# ardugilla-ver8.net
KiCad netlist of a schematic drawn in EAGLE
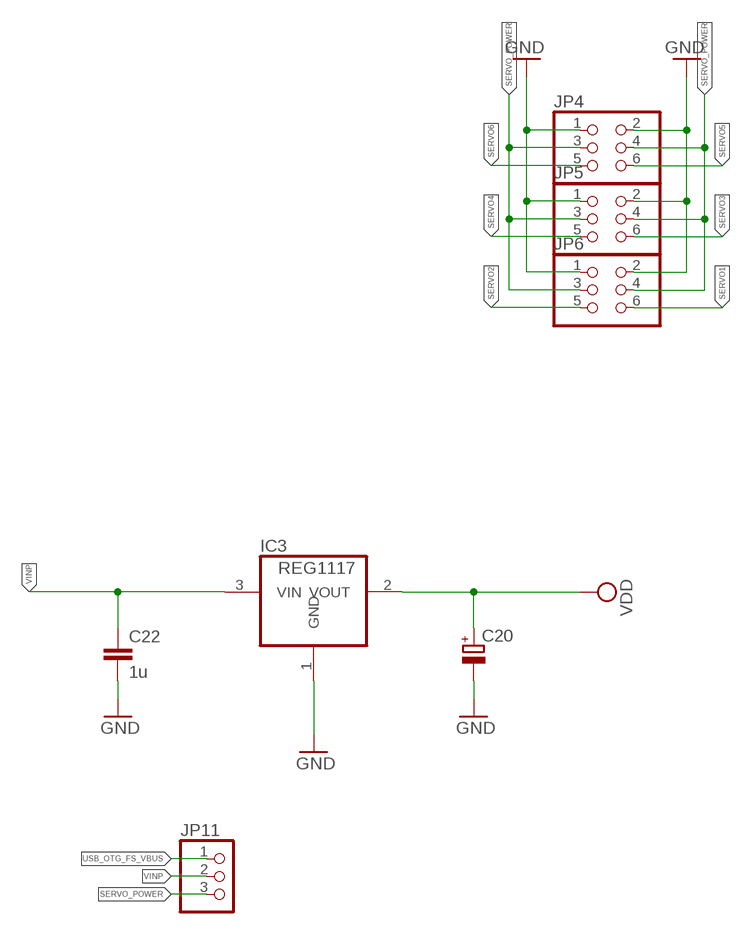
[diagram p0: schematic, sheet 1, part 1 of 2]
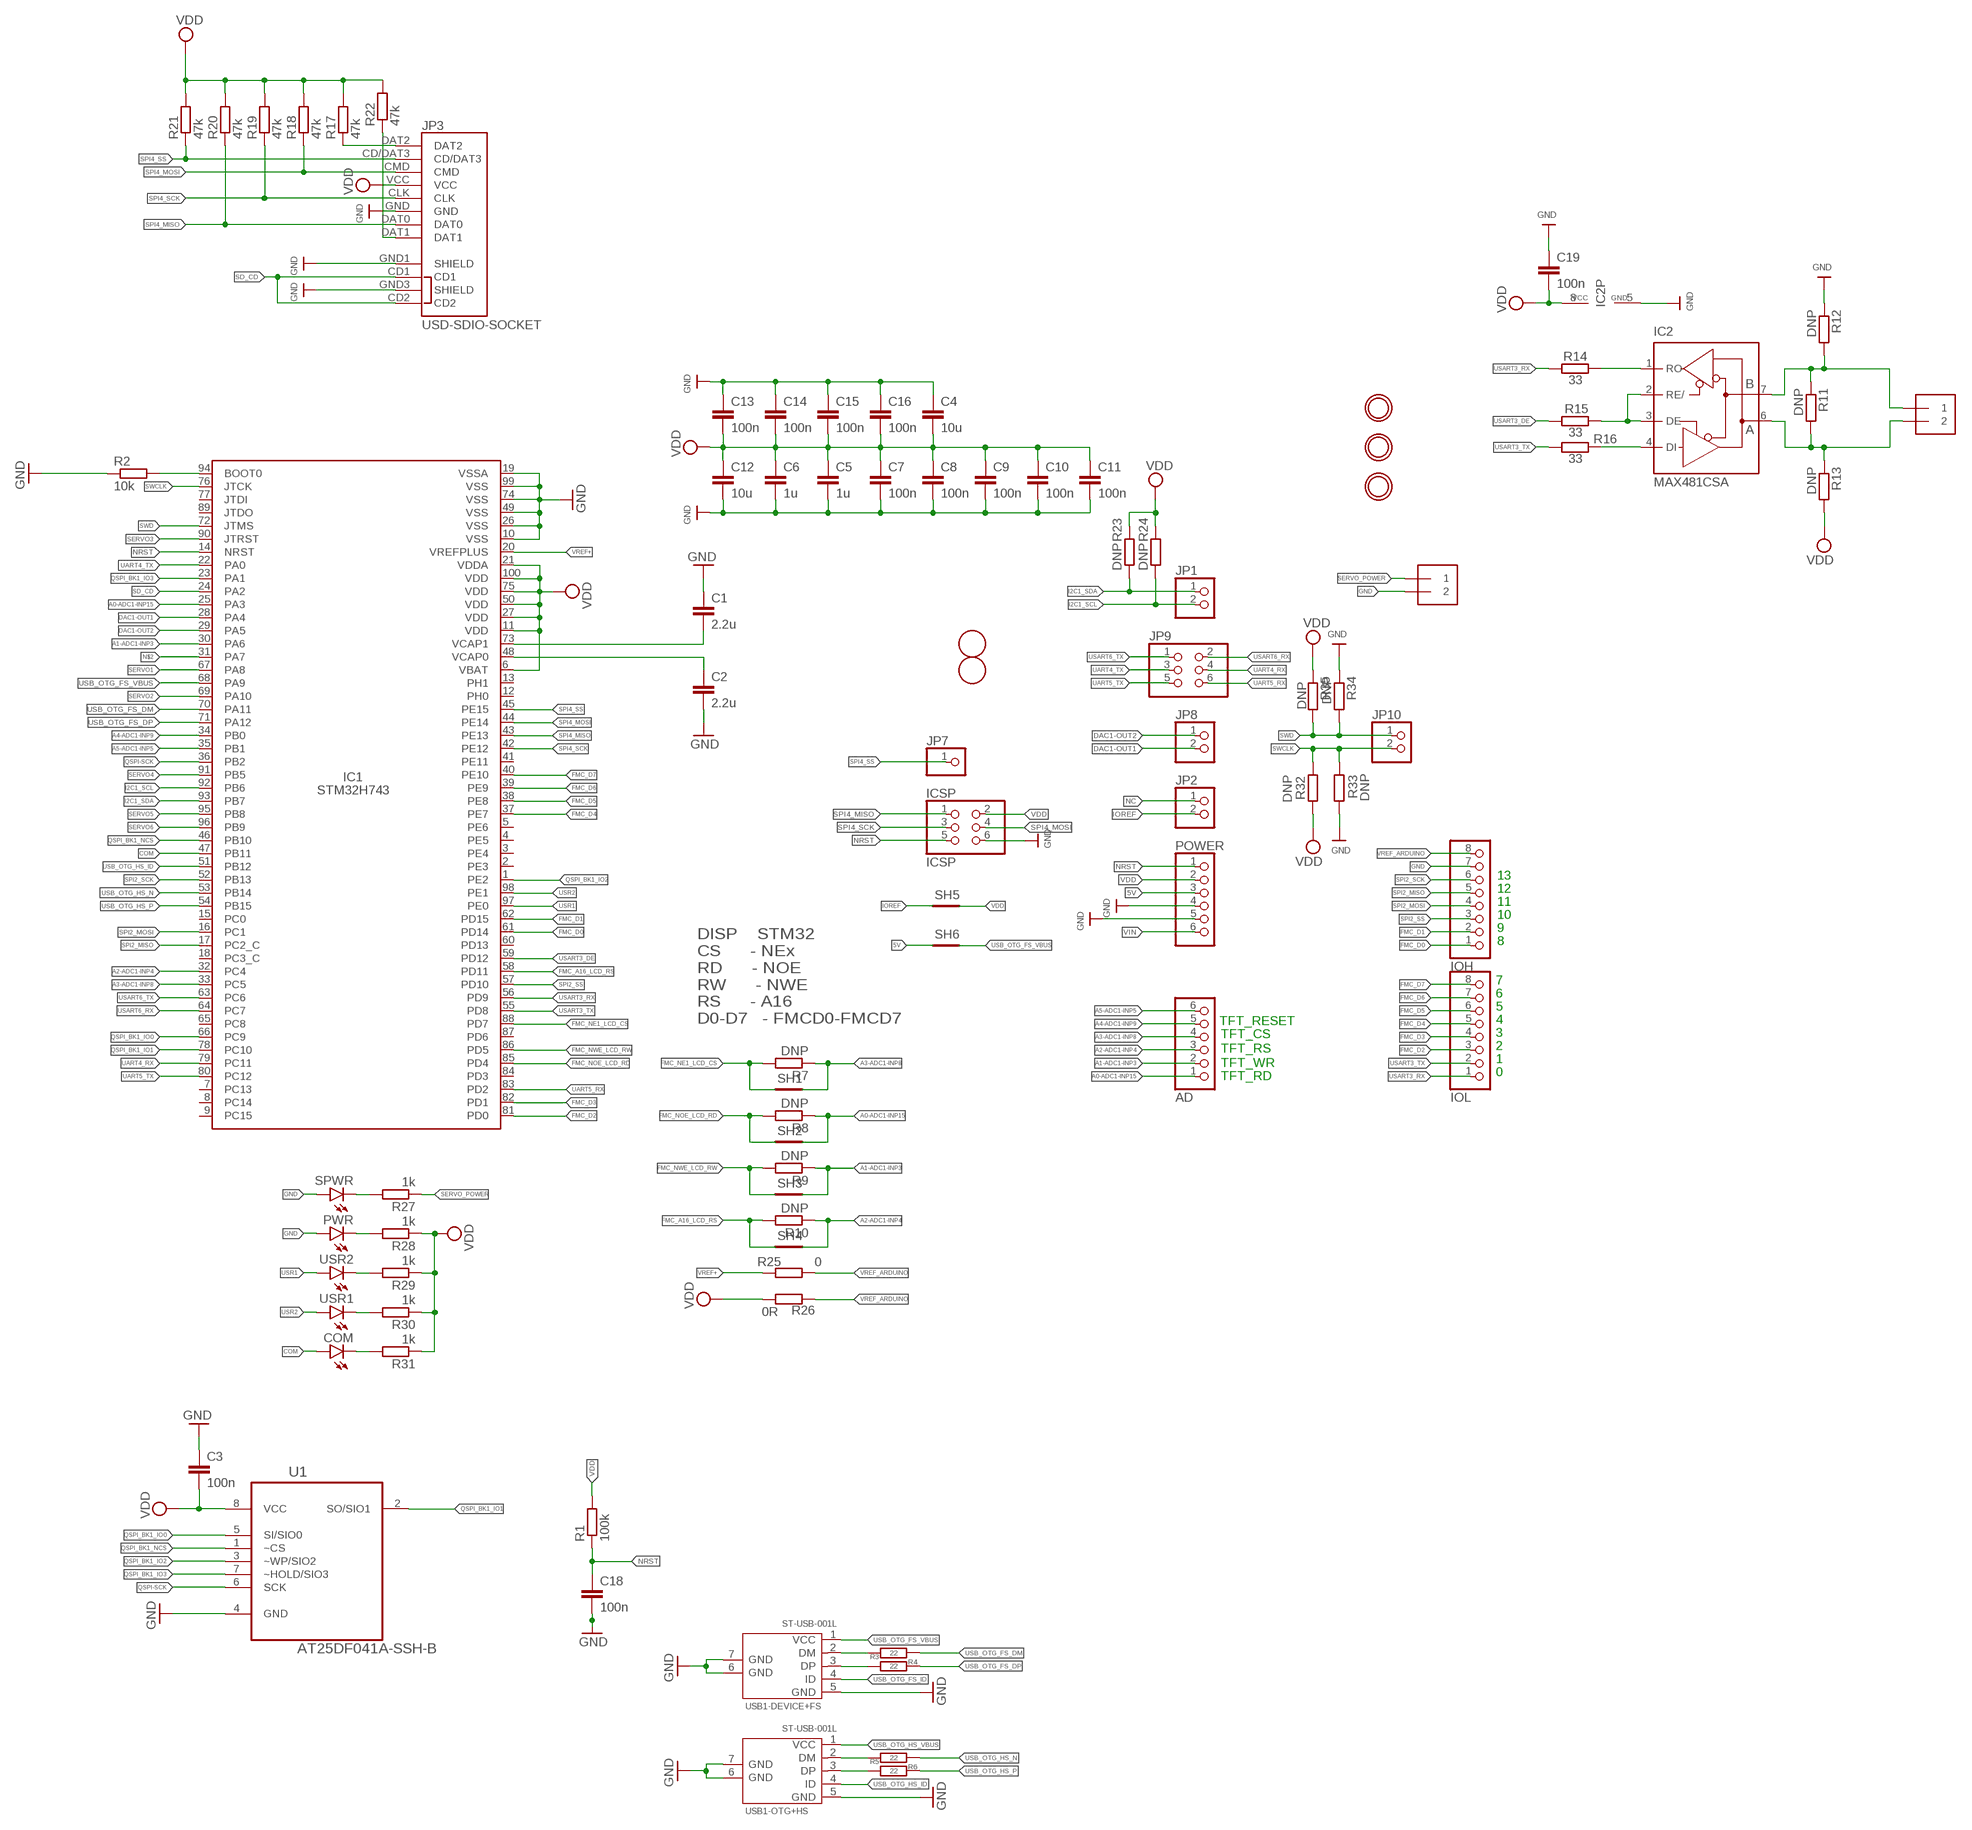
[diagram p1: schematic, sheet 1, part 2 of 2]

(export (version "E")
  (design (tool "Eeschema 10.0.6"))
  (components
    (comp (ref "AD")
      (value "PINHD-1X6")
      (footprint "eagle-import:1X06")
      (libsource (lib "eagle-import") (part "PINHD-1X6"))
    )
    (comp (ref "C1")
      (value "2.2u")
      (footprint "eagle-import:C0603")
      (libsource (lib "eagle-import") (part "C-EUC0603"))
    )
    (comp (ref "C2")
      (value "2.2u")
      (footprint "eagle-import:C0603")
      (libsource (lib "eagle-import") (part "C-EUC0603"))
    )
    (comp (ref "C3")
      (value "100n")
      (footprint "eagle-import:C0603")
      (libsource (lib "eagle-import") (part "C-EUC0603"))
    )
    (comp (ref "C4")
      (value "10u")
      (footprint "eagle-import:C0603")
      (libsource (lib "eagle-import") (part "C-EUC0603"))
    )
    (comp (ref "C5")
      (value "1u")
      (footprint "eagle-import:C0603")
      (libsource (lib "eagle-import") (part "C-EUC0603"))
    )
    (comp (ref "C6")
      (value "1u")
      (footprint "eagle-import:C0603")
      (libsource (lib "eagle-import") (part "C-EUC0603"))
    )
    (comp (ref "C7")
      (value "100n")
      (footprint "eagle-import:C0603")
      (libsource (lib "eagle-import") (part "C-EUC0603"))
    )
    (comp (ref "C8")
      (value "100n")
      (footprint "eagle-import:C0603")
      (libsource (lib "eagle-import") (part "C-EUC0603"))
    )
    (comp (ref "C9")
      (value "100n")
      (footprint "eagle-import:C0603")
      (libsource (lib "eagle-import") (part "C-EUC0603"))
    )
    (comp (ref "C10")
      (value "100n")
      (footprint "eagle-import:C0603")
      (libsource (lib "eagle-import") (part "C-EUC0603"))
    )
    (comp (ref "C11")
      (value "100n")
      (footprint "eagle-import:C0603")
      (libsource (lib "eagle-import") (part "C-EUC0603"))
    )
    (comp (ref "C12")
      (value "10u")
      (footprint "eagle-import:C0603")
      (libsource (lib "eagle-import") (part "C-EUC0603"))
    )
    (comp (ref "C13")
      (value "100n")
      (footprint "eagle-import:C0603")
      (libsource (lib "eagle-import") (part "C-EUC0603"))
    )
    (comp (ref "C14")
      (value "100n")
      (footprint "eagle-import:C0603")
      (libsource (lib "eagle-import") (part "C-EUC0603"))
    )
    (comp (ref "C15")
      (value "100n")
      (footprint "eagle-import:C0603")
      (libsource (lib "eagle-import") (part "C-EUC0603"))
    )
    (comp (ref "C16")
      (value "100n")
      (footprint "eagle-import:C0603")
      (libsource (lib "eagle-import") (part "C-EUC0603"))
    )
    (comp (ref "C18")
      (value "100n")
      (footprint "eagle-import:C0603")
      (libsource (lib "eagle-import") (part "C-EUC0603"))
    )
    (comp (ref "C19")
      (value "100n")
      (footprint "eagle-import:C0603")
      (libsource (lib "eagle-import") (part "C-EUC0603"))
    )
    (comp (ref "C20")
      (value "CPOL-EUE2-4")
      (footprint "eagle-import:E2-4")
      (libsource (lib "eagle-import") (part "CPOL-EUE2-4"))
    )
    (comp (ref "C22")
      (value "1u")
      (footprint "eagle-import:C0603")
      (libsource (lib "eagle-import") (part "C-EUC0603"))
    )
    (comp (ref "COM")
      (value "LEDSML0603")
      (footprint "eagle-import:SML0603")
      (libsource (lib "eagle-import") (part "LEDSML0603"))
    )
    (comp (ref "IC1")
      (value "STM32H743")
      (footprint "eagle-import:LQFP100_PACKAGE")
      (libsource (lib "eagle-import") (part "STM32H743_753_LQFP100"))
    )
    (comp (ref "IC2")
      (value "MAX481CSA")
      (footprint "eagle-import:SO08")
      (fields (field (name "MF") "MAXIM"))
      (libsource (lib "eagle-import") (part "MAX481CSA"))
    )
    (comp (ref "IC3")
      (value "REG1117")
      (footprint "eagle-import:SOT223")
      (libsource (lib "eagle-import") (part "REG1117"))
    )
    (comp (ref "ICSP")
      (value "ICSP")
      (footprint "eagle-import:2X03")
      (libsource (lib "eagle-import") (part "PINHD-2X3"))
    )
    (comp (ref "IOH")
      (value "PINHD-1X8")
      (footprint "eagle-import:1X08")
      (libsource (lib "eagle-import") (part "PINHD-1X8"))
    )
    (comp (ref "IOL")
      (value "PINHD-1X8")
      (footprint "eagle-import:1X08")
      (libsource (lib "eagle-import") (part "PINHD-1X8"))
    )
    (comp (ref "J1")
      (value "1X2-3.5MM")
      (footprint "eagle-import:1X2-3.5MM")
      (libsource (lib "eagle-import") (part "1X2-3.5MM"))
    )
    (comp (ref "J2")
      (value "1X2-3.5MM")
      (footprint "eagle-import:1X2-3.5MM")
      (libsource (lib "eagle-import") (part "1X2-3.5MM"))
    )
    (comp (ref "JP1")
      (value "PINHD-1X2")
      (footprint "eagle-import:1X02")
      (libsource (lib "eagle-import") (part "PINHD-1X2"))
    )
    (comp (ref "JP2")
      (value "PINHD-1X2")
      (footprint "eagle-import:1X02")
      (libsource (lib "eagle-import") (part "PINHD-1X2"))
    )
    (comp (ref "JP3")
      (value "USD-SDIO-SOCKET")
      (footprint "eagle-import:MICRO-SD-SOCKET-SDIO")
      (libsource (lib "eagle-import") (part "USD-SDIO-SOCKET"))
    )
    (comp (ref "JP4")
      (value "PINHD-2X3")
      (footprint "eagle-import:2X03")
      (libsource (lib "eagle-import") (part "PINHD-2X3"))
    )
    (comp (ref "JP5")
      (value "PINHD-2X3")
      (footprint "eagle-import:2X03")
      (libsource (lib "eagle-import") (part "PINHD-2X3"))
    )
    (comp (ref "JP6")
      (value "PINHD-2X3")
      (footprint "eagle-import:2X03")
      (libsource (lib "eagle-import") (part "PINHD-2X3"))
    )
    (comp (ref "JP7")
      (value "PINHD-1X1CB")
      (footprint "eagle-import:1X01-CLEANBIG")
      (libsource (lib "eagle-import") (part "PINHD-1X1CB"))
    )
    (comp (ref "JP8")
      (value "PINHD-1X2")
      (footprint "eagle-import:1X02")
      (libsource (lib "eagle-import") (part "PINHD-1X2"))
    )
    (comp (ref "JP9")
      (value "PINHD-2X03_2.54-90°")
      (footprint "eagle-import:2X03_90")
      (libsource (lib "eagle-import") (part "PINHD-2X03_2.54-90°"))
    )
    (comp (ref "JP10")
      (value "PINHD-1X2")
      (footprint "eagle-import:1X02")
      (libsource (lib "eagle-import") (part "PINHD-1X2"))
    )
    (comp (ref "JP11")
      (value "PINHD-1X3")
      (footprint "eagle-import:1X03")
      (libsource (lib "eagle-import") (part "PINHD-1X3"))
    )
    (comp (ref "POWER")
      (value "PINHD-1X6")
      (footprint "eagle-import:1X06")
      (libsource (lib "eagle-import") (part "PINHD-1X6"))
    )
    (comp (ref "PWR")
      (value "LEDSML0603")
      (footprint "eagle-import:SML0603")
      (libsource (lib "eagle-import") (part "LEDSML0603"))
    )
    (comp (ref "R1")
      (value "100k")
      (footprint "eagle-import:R0603")
      (libsource (lib "eagle-import") (part "R-EU_R0603"))
    )
    (comp (ref "R2")
      (value "10k")
      (footprint "eagle-import:R0603")
      (libsource (lib "eagle-import") (part "R-EU_R0603"))
    )
    (comp (ref "R3")
      (value "22")
      (footprint "eagle-import:R0603")
      (libsource (lib "eagle-import") (part "R-EU_R0603"))
    )
    (comp (ref "R4")
      (value "22")
      (footprint "eagle-import:R0603")
      (libsource (lib "eagle-import") (part "R-EU_R0603"))
    )
    (comp (ref "R5")
      (value "22")
      (footprint "eagle-import:R0603")
      (libsource (lib "eagle-import") (part "R-EU_R0603"))
    )
    (comp (ref "R6")
      (value "22")
      (footprint "eagle-import:R0603")
      (libsource (lib "eagle-import") (part "R-EU_R0603"))
    )
    (comp (ref "R7")
      (value "DNP")
      (footprint "eagle-import:R0402")
      (libsource (lib "eagle-import") (part "R-EU_R0402"))
    )
    (comp (ref "R8")
      (value "DNP")
      (footprint "eagle-import:R0402")
      (libsource (lib "eagle-import") (part "R-EU_R0402"))
    )
    (comp (ref "R9")
      (value "DNP")
      (footprint "eagle-import:R0402")
      (libsource (lib "eagle-import") (part "R-EU_R0402"))
    )
    (comp (ref "R10")
      (value "DNP")
      (footprint "eagle-import:R0402")
      (libsource (lib "eagle-import") (part "R-EU_R0402"))
    )
    (comp (ref "R11")
      (value "DNP")
      (footprint "eagle-import:R0603")
      (libsource (lib "eagle-import") (part "R-EU_R0603"))
    )
    (comp (ref "R12")
      (value "DNP")
      (footprint "eagle-import:R0603")
      (libsource (lib "eagle-import") (part "R-EU_R0603"))
    )
    (comp (ref "R13")
      (value "DNP")
      (footprint "eagle-import:R0603")
      (libsource (lib "eagle-import") (part "R-EU_R0603"))
    )
    (comp (ref "R14")
      (value "33")
      (footprint "eagle-import:R0402")
      (libsource (lib "eagle-import") (part "R-EU_R0402"))
    )
    (comp (ref "R15")
      (value "33")
      (footprint "eagle-import:R0402")
      (libsource (lib "eagle-import") (part "R-EU_R0402"))
    )
    (comp (ref "R16")
      (value "33")
      (footprint "eagle-import:R0402")
      (libsource (lib "eagle-import") (part "R-EU_R0402"))
    )
    (comp (ref "R17")
      (value "47k")
      (footprint "eagle-import:R0603")
      (libsource (lib "eagle-import") (part "R-EU_R0603"))
    )
    (comp (ref "R18")
      (value "47k")
      (footprint "eagle-import:R0603")
      (libsource (lib "eagle-import") (part "R-EU_R0603"))
    )
    (comp (ref "R19")
      (value "47k")
      (footprint "eagle-import:R0603")
      (libsource (lib "eagle-import") (part "R-EU_R0603"))
    )
    (comp (ref "R20")
      (value "47k")
      (footprint "eagle-import:R0603")
      (libsource (lib "eagle-import") (part "R-EU_R0603"))
    )
    (comp (ref "R21")
      (value "47k")
      (footprint "eagle-import:R0603")
      (libsource (lib "eagle-import") (part "R-EU_R0603"))
    )
    (comp (ref "R22")
      (value "47k")
      (footprint "eagle-import:R0603")
      (libsource (lib "eagle-import") (part "R-EU_R0603"))
    )
    (comp (ref "R23")
      (value "DNP")
      (footprint "eagle-import:R0603")
      (libsource (lib "eagle-import") (part "R-EU_R0603"))
    )
    (comp (ref "R24")
      (value "DNP")
      (footprint "eagle-import:R0603")
      (libsource (lib "eagle-import") (part "R-EU_R0603"))
    )
    (comp (ref "R25")
      (value "0")
      (footprint "eagle-import:R0603")
      (libsource (lib "eagle-import") (part "R-EU_R0603"))
    )
    (comp (ref "R26")
      (value "0R")
      (footprint "eagle-import:R0603")
      (libsource (lib "eagle-import") (part "R-EU_R0603"))
    )
    (comp (ref "R27")
      (value "1k")
      (footprint "eagle-import:R0402")
      (libsource (lib "eagle-import") (part "R-EU_R0402"))
    )
    (comp (ref "R28")
      (value "1k")
      (footprint "eagle-import:R0603")
      (libsource (lib "eagle-import") (part "R-EU_R0603"))
    )
    (comp (ref "R29")
      (value "1k")
      (footprint "eagle-import:R0402")
      (libsource (lib "eagle-import") (part "R-EU_R0402"))
    )
    (comp (ref "R30")
      (value "1k")
      (footprint "eagle-import:R0402")
      (libsource (lib "eagle-import") (part "R-EU_R0402"))
    )
    (comp (ref "R31")
      (value "1k")
      (footprint "eagle-import:R0603")
      (libsource (lib "eagle-import") (part "R-EU_R0603"))
    )
    (comp (ref "R32")
      (value "DNP")
      (footprint "eagle-import:R0603")
      (libsource (lib "eagle-import") (part "R-EU_R0603"))
    )
    (comp (ref "R33")
      (value "DNP")
      (footprint "eagle-import:R0603")
      (libsource (lib "eagle-import") (part "R-EU_R0603"))
    )
    (comp (ref "R34")
      (value "DNP")
      (footprint "eagle-import:R0603")
      (libsource (lib "eagle-import") (part "R-EU_R0603"))
    )
    (comp (ref "R35")
      (value "DNP")
      (footprint "eagle-import:R0603")
      (libsource (lib "eagle-import") (part "R-EU_R0603"))
    )
    (comp (ref "SH1")
      (value "SHORTT5")
      (footprint "eagle-import:SHORT_TOP-50")
      (libsource (lib "eagle-import") (part "SHORTT5"))
    )
    (comp (ref "SH2")
      (value "SHORTT5")
      (footprint "eagle-import:SHORT_TOP-50")
      (libsource (lib "eagle-import") (part "SHORTT5"))
    )
    (comp (ref "SH3")
      (value "SHORTT5")
      (footprint "eagle-import:SHORT_TOP-50")
      (libsource (lib "eagle-import") (part "SHORTT5"))
    )
    (comp (ref "SH4")
      (value "SHORTT5")
      (footprint "eagle-import:SHORT_TOP-50")
      (libsource (lib "eagle-import") (part "SHORTT5"))
    )
    (comp (ref "SH5")
      (value "SHORTT5")
      (footprint "eagle-import:SHORT_TOP-50")
      (libsource (lib "eagle-import") (part "SHORTT5"))
    )
    (comp (ref "SH6")
      (value "SHORTT5")
      (footprint "eagle-import:SHORT_TOP-50")
      (libsource (lib "eagle-import") (part "SHORTT5"))
    )
    (comp (ref "SPWR")
      (value "LEDSML0603")
      (footprint "eagle-import:SML0603")
      (libsource (lib "eagle-import") (part "LEDSML0603"))
    )
    (comp (ref "U$3")
      (value "FIDUCIALMOUNT")
      (footprint "eagle-import:FIDUCIA-MOUNT")
      (libsource (lib "eagle-import") (part "FIDUCIALMOUNT"))
    )
    (comp (ref "U$4")
      (value "FIDUCIALMOUNT")
      (footprint "eagle-import:FIDUCIA-MOUNT")
      (libsource (lib "eagle-import") (part "FIDUCIALMOUNT"))
    )
    (comp (ref "U$12")
      (value "MICROBUILDER_MOUNTINGHOLE3.0THIN")
      (footprint "eagle-import:MICROBUILDER_MOUNTINGHOLE_3.0_PLATEDTHIN")
      (libsource (lib "eagle-import") (part "MICROBUILDER_MOUNTINGHOLE3.0THIN"))
    )
    (comp (ref "U$13")
      (value "MICROBUILDER_MOUNTINGHOLE3.0THIN")
      (footprint "eagle-import:MICROBUILDER_MOUNTINGHOLE_3.0_PLATEDTHIN")
      (libsource (lib "eagle-import") (part "MICROBUILDER_MOUNTINGHOLE3.0THIN"))
    )
    (comp (ref "U$14")
      (value "MICROBUILDER_MOUNTINGHOLE3.0THIN")
      (footprint "eagle-import:MICROBUILDER_MOUNTINGHOLE_3.0_PLATEDTHIN")
      (libsource (lib "eagle-import") (part "MICROBUILDER_MOUNTINGHOLE3.0THIN"))
    )
    (comp (ref "U1")
      (value "AT25DF041A-SSH-B")
      (footprint "eagle-import:SOIC127P600X175-8N")
      (libsource (lib "eagle-import") (part "AT25DF041A-SSH-B"))
    )
    (comp (ref "USB1-DEVICE+FS")
      (value "ST-USB-001L")
      (footprint "eagle-import:MICRO-USB5+2P-SMD-0.65")
      (libsource (lib "eagle-import") (part "MICRO-USB-SMD-TYPE-AB-R/A(ST-USB-001L)"))
    )
    (comp (ref "USB1-OTG+HS")
      (value "ST-USB-001L")
      (footprint "eagle-import:MICRO-USB5+2P-SMD-0.65")
      (libsource (lib "eagle-import") (part "MICRO-USB-SMD-TYPE-AB-R/A(ST-USB-001L)"))
    )
    (comp (ref "USR1")
      (value "LEDSML0603")
      (footprint "eagle-import:SML0603")
      (libsource (lib "eagle-import") (part "LEDSML0603"))
    )
    (comp (ref "USR2")
      (value "LEDSML0603")
      (footprint "eagle-import:SML0603")
      (libsource (lib "eagle-import") (part "LEDSML0603"))
    )
  )
  (nets
    (net (code "1") (name "5V") (class "Default")
      (node (ref "POWER") (pin "3") (pinfunction "3_3") (pintype "passive"))
      (node (ref "SH6") (pin "1") (pinfunction "P$1_1") (pintype "bidirectional"))
    )
    (net (code "2") (name "A0-ADC1-INP15") (class "Default")
      (node (ref "AD") (pin "1") (pinfunction "1_1") (pintype "passive"))
      (node (ref "IC1") (pin "25") (pinfunction "PA3_25") (pintype "bidirectional"))
      (node (ref "R8") (pin "1") (pinfunction "1_1") (pintype "passive"))
      (node (ref "SH2") (pin "2") (pinfunction "P$2_2") (pintype "bidirectional"))
    )
    (net (code "3") (name "A1-ADC1-INP3") (class "Default")
      (node (ref "AD") (pin "2") (pinfunction "2_2") (pintype "passive"))
      (node (ref "IC1") (pin "30") (pinfunction "PA6_30") (pintype "bidirectional"))
      (node (ref "R9") (pin "1") (pinfunction "1_1") (pintype "passive"))
      (node (ref "SH3") (pin "2") (pinfunction "P$2_2") (pintype "bidirectional"))
    )
    (net (code "4") (name "A2-ADC1-INP4") (class "Default")
      (node (ref "AD") (pin "3") (pinfunction "3_3") (pintype "passive"))
      (node (ref "IC1") (pin "32") (pinfunction "PC4_32") (pintype "bidirectional"))
      (node (ref "R10") (pin "1") (pinfunction "1_1") (pintype "passive"))
      (node (ref "SH4") (pin "2") (pinfunction "P$2_2") (pintype "bidirectional"))
    )
    (net (code "5") (name "A3-ADC1-INP8") (class "Default")
      (node (ref "AD") (pin "4") (pinfunction "4_4") (pintype "passive"))
      (node (ref "IC1") (pin "33") (pinfunction "PC5_33") (pintype "bidirectional"))
      (node (ref "R7") (pin "1") (pinfunction "1_1") (pintype "passive"))
      (node (ref "SH1") (pin "2") (pinfunction "P$2_2") (pintype "bidirectional"))
    )
    (net (code "6") (name "A4-ADC1-INP9") (class "Default")
      (node (ref "AD") (pin "5") (pinfunction "5_5") (pintype "passive"))
      (node (ref "IC1") (pin "34") (pinfunction "PB0_34") (pintype "bidirectional"))
    )
    (net (code "7") (name "A5-ADC1-INP5") (class "Default")
      (node (ref "AD") (pin "6") (pinfunction "6_6") (pintype "passive"))
      (node (ref "IC1") (pin "35") (pinfunction "PB1_35") (pintype "bidirectional"))
    )
    (net (code "8") (name "COM") (class "Default")
      (node (ref "COM") (pin "A") (pinfunction "A_A") (pintype "passive"))
      (node (ref "IC1") (pin "47") (pinfunction "PB11_47") (pintype "bidirectional"))
    )
    (net (code "9") (name "DAC1-OUT1") (class "Default")
      (node (ref "IC1") (pin "28") (pinfunction "PA4_28") (pintype "bidirectional"))
      (node (ref "JP8") (pin "2") (pinfunction "2_2") (pintype "passive"))
    )
    (net (code "10") (name "DAC1-OUT2") (class "Default")
      (node (ref "IC1") (pin "29") (pinfunction "PA5_29") (pintype "bidirectional"))
      (node (ref "JP8") (pin "1") (pinfunction "1_1") (pintype "passive"))
    )
    (net (code "11") (name "FMC_A16_LCD_RS") (class "Default")
      (node (ref "IC1") (pin "58") (pinfunction "PD11_58") (pintype "bidirectional"))
      (node (ref "R10") (pin "2") (pinfunction "2_2") (pintype "passive"))
      (node (ref "SH4") (pin "1") (pinfunction "P$1_1") (pintype "bidirectional"))
    )
    (net (code "12") (name "FMC_D0") (class "Default")
      (node (ref "IC1") (pin "61") (pinfunction "PD14_61") (pintype "bidirectional"))
      (node (ref "IOH") (pin "1") (pinfunction "1_1") (pintype "passive"))
    )
    (net (code "13") (name "FMC_D1") (class "Default")
      (node (ref "IC1") (pin "62") (pinfunction "PD15_62") (pintype "bidirectional"))
      (node (ref "IOH") (pin "2") (pinfunction "2_2") (pintype "passive"))
    )
    (net (code "14") (name "FMC_D2") (class "Default")
      (node (ref "IC1") (pin "81") (pinfunction "PD0_81") (pintype "bidirectional"))
      (node (ref "IOL") (pin "3") (pinfunction "3_3") (pintype "passive"))
    )
    (net (code "15") (name "FMC_D3") (class "Default")
      (node (ref "IC1") (pin "82") (pinfunction "PD1_82") (pintype "bidirectional"))
      (node (ref "IOL") (pin "4") (pinfunction "4_4") (pintype "passive"))
    )
    (net (code "16") (name "FMC_D4") (class "Default")
      (node (ref "IC1") (pin "37") (pinfunction "PE7_37") (pintype "bidirectional"))
      (node (ref "IOL") (pin "5") (pinfunction "5_5") (pintype "passive"))
    )
    (net (code "17") (name "FMC_D5") (class "Default")
      (node (ref "IC1") (pin "38") (pinfunction "PE8_38") (pintype "bidirectional"))
      (node (ref "IOL") (pin "6") (pinfunction "6_6") (pintype "passive"))
    )
    (net (code "18") (name "FMC_D6") (class "Default")
      (node (ref "IC1") (pin "39") (pinfunction "PE9_39") (pintype "bidirectional"))
      (node (ref "IOL") (pin "7") (pinfunction "7_7") (pintype "passive"))
    )
    (net (code "19") (name "FMC_D7") (class "Default")
      (node (ref "IC1") (pin "40") (pinfunction "PE10_40") (pintype "bidirectional"))
      (node (ref "IOL") (pin "8") (pinfunction "8_8") (pintype "passive"))
    )
    (net (code "20") (name "FMC_NE1_LCD_CS") (class "Default")
      (node (ref "IC1") (pin "88") (pinfunction "PD7_88") (pintype "bidirectional"))
      (node (ref "R7") (pin "2") (pinfunction "2_2") (pintype "passive"))
      (node (ref "SH1") (pin "1") (pinfunction "P$1_1") (pintype "bidirectional"))
    )
    (net (code "21") (name "FMC_NOE_LCD_RD") (class "Default")
      (node (ref "IC1") (pin "85") (pinfunction "PD4_85") (pintype "bidirectional"))
      (node (ref "R8") (pin "2") (pinfunction "2_2") (pintype "passive"))
      (node (ref "SH2") (pin "1") (pinfunction "P$1_1") (pintype "bidirectional"))
    )
    (net (code "22") (name "FMC_NWE_LCD_RW") (class "Default")
      (node (ref "IC1") (pin "86") (pinfunction "PD5_86") (pintype "bidirectional"))
      (node (ref "R9") (pin "2") (pinfunction "2_2") (pintype "passive"))
      (node (ref "SH3") (pin "1") (pinfunction "P$1_1") (pintype "bidirectional"))
    )
    (net (code "23") (name "GND") (class "Default")
      (node (ref "C1") (pin "1") (pinfunction "1_1") (pintype "passive"))
      (node (ref "C10") (pin "2") (pinfunction "2_2") (pintype "passive"))
      (node (ref "C11") (pin "2") (pinfunction "2_2") (pintype "passive"))
      (node (ref "C12") (pin "2") (pinfunction "2_2") (pintype "passive"))
      (node (ref "C13") (pin "1") (pinfunction "1_1") (pintype "passive"))
      (node (ref "C14") (pin "1") (pinfunction "1_1") (pintype "passive"))
      (node (ref "C15") (pin "1") (pinfunction "1_1") (pintype "passive"))
      (node (ref "C16") (pin "1") (pinfunction "1_1") (pintype "passive"))
      (node (ref "C18") (pin "2") (pinfunction "2_2") (pintype "passive"))
      (node (ref "C19") (pin "1") (pinfunction "1_1") (pintype "passive"))
      (node (ref "C2") (pin "2") (pinfunction "2_2") (pintype "passive"))
      (node (ref "C20") (pin "-") (pinfunction "-_-") (pintype "passive"))
      (node (ref "C22") (pin "2") (pinfunction "2_2") (pintype "passive"))
      (node (ref "C3") (pin "1") (pinfunction "1_1") (pintype "passive"))
      (node (ref "C4") (pin "1") (pinfunction "1_1") (pintype "passive"))
      (node (ref "C5") (pin "2") (pinfunction "2_2") (pintype "passive"))
      (node (ref "C6") (pin "2") (pinfunction "2_2") (pintype "passive"))
      (node (ref "C7") (pin "2") (pinfunction "2_2") (pintype "passive"))
      (node (ref "C8") (pin "2") (pinfunction "2_2") (pintype "passive"))
      (node (ref "C9") (pin "2") (pinfunction "2_2") (pintype "passive"))
      (node (ref "IC1") (pin "10") (pinfunction "VSS_10") (pintype "power_in"))
      (node (ref "IC1") (pin "19") (pinfunction "VSSA_19") (pintype "power_in"))
      (node (ref "IC1") (pin "26") (pinfunction "VSS_26") (pintype "power_in"))
      (node (ref "IC1") (pin "49") (pinfunction "VSS_49") (pintype "power_in"))
      (node (ref "IC1") (pin "74") (pinfunction "VSS_74") (pintype "power_in"))
      (node (ref "IC1") (pin "99") (pinfunction "VSS_99") (pintype "power_in"))
      (node (ref "IC2") (pin "5") (pinfunction "GND_5") (pintype "power_in"))
      (node (ref "IC3") (pin "1") (pinfunction "GND_1") (pintype "power_in"))
      (node (ref "ICSP") (pin "6") (pinfunction "6_6") (pintype "passive"))
      (node (ref "IOH") (pin "7") (pinfunction "7_7") (pintype "passive"))
      (node (ref "J2") (pin "2") (pinfunction "2_2") (pintype "passive"))
      (node (ref "JP3") (pin "GND") (pinfunction "GND_GND") (pintype "bidirectional"))
      (node (ref "JP3") (pin "GND1") (pinfunction "SHIELD_GND1") (pintype "bidirectional"))
      (node (ref "JP3") (pin "GND3") (pinfunction "SHIELD_GND3") (pintype "bidirectional"))
      (node (ref "JP4") (pin "1") (pinfunction "1_1") (pintype "passive"))
      (node (ref "JP4") (pin "2") (pinfunction "2_2") (pintype "passive"))
      (node (ref "JP5") (pin "1") (pinfunction "1_1") (pintype "passive"))
      (node (ref "JP5") (pin "2") (pinfunction "2_2") (pintype "passive"))
      (node (ref "JP6") (pin "1") (pinfunction "1_1") (pintype "passive"))
      (node (ref "JP6") (pin "2") (pinfunction "2_2") (pintype "passive"))
      (node (ref "POWER") (pin "4") (pinfunction "4_4") (pintype "passive"))
      (node (ref "POWER") (pin "5") (pinfunction "5_5") (pintype "passive"))
      (node (ref "PWR") (pin "A") (pinfunction "A_A") (pintype "passive"))
      (node (ref "R12") (pin "1") (pinfunction "1_1") (pintype "passive"))
      (node (ref "R2") (pin "1") (pinfunction "1_1") (pintype "passive"))
      (node (ref "R33") (pin "2") (pinfunction "2_2") (pintype "passive"))
      (node (ref "R34") (pin "1") (pinfunction "1_1") (pintype "passive"))
      (node (ref "SPWR") (pin "A") (pinfunction "A_A") (pintype "passive"))
      (node (ref "U1") (pin "4") (pinfunction "GND_4") (pintype "passive"))
      (node (ref "USB1-DEVICE+FS") (pin "5") (pinfunction "GND_5") (pintype "bidirectional"))
      (node (ref "USB1-DEVICE+FS") (pin "6") (pinfunction "GND_6") (pintype "bidirectional"))
      (node (ref "USB1-DEVICE+FS") (pin "7") (pinfunction "GND_7") (pintype "bidirectional"))
      (node (ref "USB1-OTG+HS") (pin "5") (pinfunction "GND_5") (pintype "bidirectional"))
      (node (ref "USB1-OTG+HS") (pin "6") (pinfunction "GND_6") (pintype "bidirectional"))
      (node (ref "USB1-OTG+HS") (pin "7") (pinfunction "GND_7") (pintype "bidirectional"))
    )
    (net (code "24") (name "I2C1_SCL") (class "Default")
      (node (ref "IC1") (pin "92") (pinfunction "PB6_92") (pintype "bidirectional"))
      (node (ref "JP1") (pin "2") (pinfunction "2_2") (pintype "passive"))
      (node (ref "R24") (pin "1") (pinfunction "1_1") (pintype "passive"))
    )
    (net (code "25") (name "I2C1_SDA") (class "Default")
      (node (ref "IC1") (pin "93") (pinfunction "PB7_93") (pintype "bidirectional"))
      (node (ref "JP1") (pin "1") (pinfunction "1_1") (pintype "passive"))
      (node (ref "R23") (pin "1") (pinfunction "1_1") (pintype "passive"))
    )
    (net (code "26") (name "IOREF") (class "Default")
      (node (ref "JP2") (pin "2") (pinfunction "2_2") (pintype "passive"))
      (node (ref "SH5") (pin "1") (pinfunction "P$1_1") (pintype "bidirectional"))
    )
    (net (code "27") (name "N$2") (class "Default")
      (node (ref "IC1") (pin "31") (pinfunction "PA7_31") (pintype "bidirectional"))
    )
    (net (code "28") (name "NC") (class "Default")
      (node (ref "JP2") (pin "1") (pinfunction "1_1") (pintype "passive"))
    )
    (net (code "29") (name "NRST") (class "Default")
      (node (ref "C18") (pin "1") (pinfunction "1_1") (pintype "passive"))
      (node (ref "IC1") (pin "14") (pinfunction "NRST_14") (pintype "input"))
      (node (ref "ICSP") (pin "5") (pinfunction "5_5") (pintype "passive"))
      (node (ref "POWER") (pin "1") (pinfunction "1_1") (pintype "passive"))
      (node (ref "R1") (pin "1") (pinfunction "1_1") (pintype "passive"))
    )
    (net (code "30") (name "Net-(COM-PadC)") (class "Default")
      (node (ref "COM") (pin "C") (pinfunction "C_C") (pintype "passive"))
      (node (ref "R31") (pin "2") (pinfunction "2_2") (pintype "passive"))
    )
    (net (code "31") (name "Net-(IC1-BOOT0)") (class "Default")
      (node (ref "IC1") (pin "94") (pinfunction "BOOT0_94") (pintype "input"))
      (node (ref "R2") (pin "2") (pinfunction "2_2") (pintype "passive"))
    )
    (net (code "32") (name "Net-(IC1-VCAP0)") (class "Default")
      (node (ref "C2") (pin "1") (pinfunction "1_1") (pintype "passive"))
      (node (ref "IC1") (pin "48") (pinfunction "VCAP0_48") (pintype "passive"))
    )
    (net (code "33") (name "Net-(IC1-VCAP1)") (class "Default")
      (node (ref "C1") (pin "2") (pinfunction "2_2") (pintype "passive"))
      (node (ref "IC1") (pin "73") (pinfunction "VCAP1_73") (pintype "passive"))
    )
    (net (code "34") (name "Net-(IC2A-A)") (class "Default")
      (node (ref "IC2") (pin "6") (pinfunction "A_6") (pintype "passive"))
      (node (ref "J1") (pin "2") (pinfunction "2_2") (pintype "passive"))
      (node (ref "R11") (pin "2") (pinfunction "2_2") (pintype "passive"))
      (node (ref "R13") (pin "1") (pinfunction "1_1") (pintype "passive"))
    )
    (net (code "35") (name "Net-(IC2A-B)") (class "Default")
      (node (ref "IC2") (pin "7") (pinfunction "B_7") (pintype "passive"))
      (node (ref "J1") (pin "1") (pinfunction "1_1") (pintype "passive"))
      (node (ref "R11") (pin "1") (pinfunction "1_1") (pintype "passive"))
      (node (ref "R12") (pin "2") (pinfunction "2_2") (pintype "passive"))
    )
    (net (code "36") (name "Net-(IC2A-DE)") (class "Default")
      (node (ref "IC2") (pin "2") (pinfunction "RE/_2") (pintype "input"))
      (node (ref "IC2") (pin "3") (pinfunction "DE_3") (pintype "input"))
      (node (ref "R15") (pin "2") (pinfunction "2_2") (pintype "passive"))
    )
    (net (code "37") (name "Net-(IC2A-DI)") (class "Default")
      (node (ref "IC2") (pin "4") (pinfunction "DI_4") (pintype "input"))
      (node (ref "R16") (pin "2") (pinfunction "2_2") (pintype "passive"))
    )
    (net (code "38") (name "Net-(IC2A-RO)") (class "Default")
      (node (ref "IC2") (pin "1") (pinfunction "RO_1") (pintype "output"))
      (node (ref "R14") (pin "2") (pinfunction "2_2") (pintype "passive"))
    )
    (net (code "39") (name "Net-(JP3-PadDAT1)") (class "Default")
      (node (ref "JP3") (pin "DAT1") (pinfunction "DAT1_DAT1") (pintype "bidirectional"))
      (node (ref "R22") (pin "1") (pinfunction "1_1") (pintype "passive"))
    )
    (net (code "40") (name "Net-(JP3-PadDAT2)") (class "Default")
      (node (ref "JP3") (pin "DAT2") (pinfunction "DAT2_DAT2") (pintype "bidirectional"))
      (node (ref "R17") (pin "1") (pinfunction "1_1") (pintype "passive"))
    )
    (net (code "41") (name "Net-(PWR-PadC)") (class "Default")
      (node (ref "PWR") (pin "C") (pinfunction "C_C") (pintype "passive"))
      (node (ref "R28") (pin "2") (pinfunction "2_2") (pintype "passive"))
    )
    (net (code "42") (name "Net-(R27-Pad2)") (class "Default")
      (node (ref "R27") (pin "2") (pinfunction "2_2") (pintype "passive"))
      (node (ref "SPWR") (pin "C") (pinfunction "C_C") (pintype "passive"))
    )
    (net (code "43") (name "Net-(R29-Pad2)") (class "Default")
      (node (ref "R29") (pin "2") (pinfunction "2_2") (pintype "passive"))
      (node (ref "USR2") (pin "C") (pinfunction "C_C") (pintype "passive"))
    )
    (net (code "44") (name "Net-(R30-Pad2)") (class "Default")
      (node (ref "R30") (pin "2") (pinfunction "2_2") (pintype "passive"))
      (node (ref "USR1") (pin "C") (pinfunction "C_C") (pintype "passive"))
    )
    (net (code "45") (name "Net-(USB1-DEVICE+FS-DM)") (class "Default")
      (node (ref "R3") (pin "2") (pinfunction "2_2") (pintype "passive"))
      (node (ref "USB1-DEVICE+FS") (pin "2") (pinfunction "DM_2") (pintype "bidirectional"))
    )
    (net (code "46") (name "Net-(USB1-DEVICE+FS-DP)") (class "Default")
      (node (ref "R4") (pin "2") (pinfunction "2_2") (pintype "passive"))
      (node (ref "USB1-DEVICE+FS") (pin "3") (pinfunction "DP_3") (pintype "bidirectional"))
    )
    (net (code "47") (name "Net-(USB1-OTG+HS-DM)") (class "Default")
      (node (ref "R5") (pin "2") (pinfunction "2_2") (pintype "passive"))
      (node (ref "USB1-OTG+HS") (pin "2") (pinfunction "DM_2") (pintype "bidirectional"))
    )
    (net (code "48") (name "Net-(USB1-OTG+HS-DP)") (class "Default")
      (node (ref "R6") (pin "2") (pinfunction "2_2") (pintype "passive"))
      (node (ref "USB1-OTG+HS") (pin "3") (pinfunction "DP_3") (pintype "bidirectional"))
    )
    (net (code "49") (name "QSPI-SCK") (class "Default")
      (node (ref "IC1") (pin "36") (pinfunction "PB2_36") (pintype "bidirectional"))
      (node (ref "U1") (pin "6") (pinfunction "SCK_6") (pintype "input"))
    )
    (net (code "50") (name "QSPI_BK1_IO0") (class "Default")
      (node (ref "IC1") (pin "66") (pinfunction "PC9_66") (pintype "bidirectional"))
      (node (ref "U1") (pin "5") (pinfunction "SI/SIO0_5") (pintype "input"))
    )
    (net (code "51") (name "QSPI_BK1_IO1") (class "Default")
      (node (ref "IC1") (pin "78") (pinfunction "PC10_78") (pintype "bidirectional"))
      (node (ref "U1") (pin "2") (pinfunction "SO/SIO1_2") (pintype "output"))
    )
    (net (code "52") (name "QSPI_BK1_IO2") (class "Default")
      (node (ref "IC1") (pin "1") (pinfunction "PE2_1") (pintype "bidirectional"))
      (node (ref "U1") (pin "3") (pinfunction "~{WP/SIO2}_3") (pintype "input"))
    )
    (net (code "53") (name "QSPI_BK1_IO3") (class "Default")
      (node (ref "IC1") (pin "23") (pinfunction "PA1_23") (pintype "bidirectional"))
      (node (ref "U1") (pin "7") (pinfunction "~{HOLD/SIO3}_7") (pintype "input"))
    )
    (net (code "54") (name "QSPI_BK1_NCS") (class "Default")
      (node (ref "IC1") (pin "46") (pinfunction "PB10_46") (pintype "bidirectional"))
      (node (ref "U1") (pin "1") (pinfunction "~{CS}_1") (pintype "input"))
    )
    (net (code "55") (name "SD_CD") (class "Default")
      (node (ref "IC1") (pin "24") (pinfunction "PA2_24") (pintype "bidirectional"))
      (node (ref "JP3") (pin "CD1") (pinfunction "CD1_CD1") (pintype "bidirectional"))
      (node (ref "JP3") (pin "CD2") (pinfunction "CD2_CD2") (pintype "bidirectional"))
    )
    (net (code "56") (name "SERVO1") (class "Default")
      (node (ref "IC1") (pin "67") (pinfunction "PA8_67") (pintype "bidirectional"))
      (node (ref "JP6") (pin "6") (pinfunction "6_6") (pintype "passive"))
    )
    (net (code "57") (name "SERVO2") (class "Default")
      (node (ref "IC1") (pin "69") (pinfunction "PA10_69") (pintype "bidirectional"))
      (node (ref "JP6") (pin "5") (pinfunction "5_5") (pintype "passive"))
    )
    (net (code "58") (name "SERVO3") (class "Default")
      (node (ref "IC1") (pin "90") (pinfunction "JTRST_90") (pintype "input"))
      (node (ref "JP5") (pin "6") (pinfunction "6_6") (pintype "passive"))
    )
    (net (code "59") (name "SERVO4") (class "Default")
      (node (ref "IC1") (pin "91") (pinfunction "PB5_91") (pintype "bidirectional"))
      (node (ref "JP5") (pin "5") (pinfunction "5_5") (pintype "passive"))
    )
    (net (code "60") (name "SERVO5") (class "Default")
      (node (ref "IC1") (pin "95") (pinfunction "PB8_95") (pintype "bidirectional"))
      (node (ref "JP4") (pin "6") (pinfunction "6_6") (pintype "passive"))
    )
    (net (code "61") (name "SERVO6") (class "Default")
      (node (ref "IC1") (pin "96") (pinfunction "PB9_96") (pintype "bidirectional"))
      (node (ref "JP4") (pin "5") (pinfunction "5_5") (pintype "passive"))
    )
    (net (code "62") (name "SERVO_POWER") (class "Default")
      (node (ref "J2") (pin "1") (pinfunction "1_1") (pintype "passive"))
      (node (ref "JP11") (pin "3") (pinfunction "3_3") (pintype "passive"))
      (node (ref "JP4") (pin "3") (pinfunction "3_3") (pintype "passive"))
      (node (ref "JP4") (pin "4") (pinfunction "4_4") (pintype "passive"))
      (node (ref "JP5") (pin "3") (pinfunction "3_3") (pintype "passive"))
      (node (ref "JP5") (pin "4") (pinfunction "4_4") (pintype "passive"))
      (node (ref "JP6") (pin "3") (pinfunction "3_3") (pintype "passive"))
      (node (ref "JP6") (pin "4") (pinfunction "4_4") (pintype "passive"))
      (node (ref "R27") (pin "1") (pinfunction "1_1") (pintype "passive"))
    )
    (net (code "63") (name "SPI2_MISO") (class "Default")
      (node (ref "IC1") (pin "17") (pinfunction "PC2_C_17") (pintype "passive"))
      (node (ref "IOH") (pin "5") (pinfunction "5_5") (pintype "passive"))
    )
    (net (code "64") (name "SPI2_MOSI") (class "Default")
      (node (ref "IC1") (pin "16") (pinfunction "PC1_16") (pintype "bidirectional"))
      (node (ref "IOH") (pin "4") (pinfunction "4_4") (pintype "passive"))
    )
    (net (code "65") (name "SPI2_SCK") (class "Default")
      (node (ref "IC1") (pin "52") (pinfunction "PB13_52") (pintype "bidirectional"))
      (node (ref "IOH") (pin "6") (pinfunction "6_6") (pintype "passive"))
    )
    (net (code "66") (name "SPI2_SS") (class "Default")
      (node (ref "IC1") (pin "57") (pinfunction "PD10_57") (pintype "bidirectional"))
      (node (ref "IOH") (pin "3") (pinfunction "3_3") (pintype "passive"))
    )
    (net (code "67") (name "SPI4_MISO") (class "Default")
      (node (ref "IC1") (pin "43") (pinfunction "PE13_43") (pintype "bidirectional"))
      (node (ref "ICSP") (pin "1") (pinfunction "1_1") (pintype "passive"))
      (node (ref "JP3") (pin "DAT0") (pinfunction "DAT0_DAT0") (pintype "bidirectional"))
      (node (ref "R20") (pin "1") (pinfunction "1_1") (pintype "passive"))
    )
    (net (code "68") (name "SPI4_MOSI") (class "Default")
      (node (ref "IC1") (pin "44") (pinfunction "PE14_44") (pintype "bidirectional"))
      (node (ref "ICSP") (pin "4") (pinfunction "4_4") (pintype "passive"))
      (node (ref "JP3") (pin "CMD") (pinfunction "CMD_CMD") (pintype "bidirectional"))
      (node (ref "R18") (pin "1") (pinfunction "1_1") (pintype "passive"))
    )
    (net (code "69") (name "SPI4_SCK") (class "Default")
      (node (ref "IC1") (pin "42") (pinfunction "PE12_42") (pintype "bidirectional"))
      (node (ref "ICSP") (pin "3") (pinfunction "3_3") (pintype "passive"))
      (node (ref "JP3") (pin "CLK") (pinfunction "CLK_CLK") (pintype "bidirectional"))
      (node (ref "R19") (pin "1") (pinfunction "1_1") (pintype "passive"))
    )
    (net (code "70") (name "SPI4_SS") (class "Default")
      (node (ref "IC1") (pin "45") (pinfunction "PE15_45") (pintype "bidirectional"))
      (node (ref "JP3") (pin "CD/DAT3") (pinfunction "CD/DAT3_CD/DAT3") (pintype "bidirectional"))
      (node (ref "JP7") (pin "1") (pinfunction "1_1") (pintype "passive"))
      (node (ref "R21") (pin "1") (pinfunction "1_1") (pintype "passive"))
    )
    (net (code "71") (name "SWCLK") (class "Default")
      (node (ref "IC1") (pin "76") (pinfunction "JTCK_76") (pintype "input"))
      (node (ref "JP10") (pin "2") (pinfunction "2_2") (pintype "passive"))
      (node (ref "R32") (pin "1") (pinfunction "1_1") (pintype "passive"))
      (node (ref "R33") (pin "1") (pinfunction "1_1") (pintype "passive"))
    )
    (net (code "72") (name "SWD") (class "Default")
      (node (ref "IC1") (pin "72") (pinfunction "JTMS_72") (pintype "input"))
      (node (ref "JP10") (pin "1") (pinfunction "1_1") (pintype "passive"))
      (node (ref "R34") (pin "2") (pinfunction "2_2") (pintype "passive"))
      (node (ref "R35") (pin "2") (pinfunction "2_2") (pintype "passive"))
    )
    (net (code "73") (name "UART4_RX") (class "Default")
      (node (ref "IC1") (pin "79") (pinfunction "PC11_79") (pintype "bidirectional"))
      (node (ref "JP9") (pin "4") (pinfunction "4_4") (pintype "passive"))
    )
    (net (code "74") (name "UART4_TX") (class "Default")
      (node (ref "IC1") (pin "22") (pinfunction "PA0_22") (pintype "bidirectional"))
      (node (ref "JP9") (pin "3") (pinfunction "3_3") (pintype "passive"))
    )
    (net (code "75") (name "UART5_RX") (class "Default")
      (node (ref "IC1") (pin "83") (pinfunction "PD2_83") (pintype "bidirectional"))
      (node (ref "JP9") (pin "6") (pinfunction "6_6") (pintype "passive"))
    )
    (net (code "76") (name "UART5_TX") (class "Default")
      (node (ref "IC1") (pin "80") (pinfunction "PC12_80") (pintype "bidirectional"))
      (node (ref "JP9") (pin "5") (pinfunction "5_5") (pintype "passive"))
    )
    (net (code "77") (name "USART3_DE") (class "Default")
      (node (ref "IC1") (pin "59") (pinfunction "PD12_59") (pintype "bidirectional"))
      (node (ref "R15") (pin "1") (pinfunction "1_1") (pintype "passive"))
    )
    (net (code "78") (name "USART3_RX") (class "Default")
      (node (ref "IC1") (pin "56") (pinfunction "PD9_56") (pintype "bidirectional"))
      (node (ref "IOL") (pin "1") (pinfunction "1_1") (pintype "passive"))
      (node (ref "R14") (pin "1") (pinfunction "1_1") (pintype "passive"))
    )
    (net (code "79") (name "USART3_TX") (class "Default")
      (node (ref "IC1") (pin "55") (pinfunction "PD8_55") (pintype "bidirectional"))
      (node (ref "IOL") (pin "2") (pinfunction "2_2") (pintype "passive"))
      (node (ref "R16") (pin "1") (pinfunction "1_1") (pintype "passive"))
    )
    (net (code "80") (name "USART6_RX") (class "Default")
      (node (ref "IC1") (pin "64") (pinfunction "PC7_64") (pintype "bidirectional"))
      (node (ref "JP9") (pin "2") (pinfunction "2_2") (pintype "passive"))
    )
    (net (code "81") (name "USART6_TX") (class "Default")
      (node (ref "IC1") (pin "63") (pinfunction "PC6_63") (pintype "bidirectional"))
      (node (ref "JP9") (pin "1") (pinfunction "1_1") (pintype "passive"))
    )
    (net (code "82") (name "USB_OTG_FS_DM") (class "Default")
      (node (ref "IC1") (pin "70") (pinfunction "PA11_70") (pintype "bidirectional"))
      (node (ref "R3") (pin "1") (pinfunction "1_1") (pintype "passive"))
    )
    (net (code "83") (name "USB_OTG_FS_DP") (class "Default")
      (node (ref "IC1") (pin "71") (pinfunction "PA12_71") (pintype "bidirectional"))
      (node (ref "R4") (pin "1") (pinfunction "1_1") (pintype "passive"))
    )
    (net (code "84") (name "USB_OTG_FS_ID") (class "Default")
      (node (ref "USB1-DEVICE+FS") (pin "4") (pinfunction "ID_4") (pintype "bidirectional"))
    )
    (net (code "85") (name "USB_OTG_FS_VBUS") (class "Default")
      (node (ref "IC1") (pin "68") (pinfunction "PA9_68") (pintype "bidirectional"))
      (node (ref "JP11") (pin "1") (pinfunction "1_1") (pintype "passive"))
      (node (ref "SH6") (pin "2") (pinfunction "P$2_2") (pintype "bidirectional"))
      (node (ref "USB1-DEVICE+FS") (pin "1") (pinfunction "VCC_1") (pintype "bidirectional"))
    )
    (net (code "86") (name "USB_OTG_HS_ID") (class "Default")
      (node (ref "IC1") (pin "51") (pinfunction "PB12_51") (pintype "bidirectional"))
      (node (ref "USB1-OTG+HS") (pin "4") (pinfunction "ID_4") (pintype "bidirectional"))
    )
    (net (code "87") (name "USB_OTG_HS_N") (class "Default")
      (node (ref "IC1") (pin "53") (pinfunction "PB14_53") (pintype "bidirectional"))
      (node (ref "R5") (pin "1") (pinfunction "1_1") (pintype "passive"))
    )
    (net (code "88") (name "USB_OTG_HS_P") (class "Default")
      (node (ref "IC1") (pin "54") (pinfunction "PB15_54") (pintype "bidirectional"))
      (node (ref "R6") (pin "1") (pinfunction "1_1") (pintype "passive"))
    )
    (net (code "89") (name "USB_OTG_HS_VBUS") (class "Default")
      (node (ref "USB1-OTG+HS") (pin "1") (pinfunction "VCC_1") (pintype "bidirectional"))
    )
    (net (code "90") (name "USR1") (class "Default")
      (node (ref "IC1") (pin "97") (pinfunction "PE0_97") (pintype "bidirectional"))
      (node (ref "USR2") (pin "A") (pinfunction "A_A") (pintype "passive"))
    )
    (net (code "91") (name "USR2") (class "Default")
      (node (ref "IC1") (pin "98") (pinfunction "PE1_98") (pintype "bidirectional"))
      (node (ref "USR1") (pin "A") (pinfunction "A_A") (pintype "passive"))
    )
    (net (code "92") (name "VDD") (class "Default")
      (node (ref "C10") (pin "1") (pinfunction "1_1") (pintype "passive"))
      (node (ref "C11") (pin "1") (pinfunction "1_1") (pintype "passive"))
      (node (ref "C12") (pin "1") (pinfunction "1_1") (pintype "passive"))
      (node (ref "C13") (pin "2") (pinfunction "2_2") (pintype "passive"))
      (node (ref "C14") (pin "2") (pinfunction "2_2") (pintype "passive"))
      (node (ref "C15") (pin "2") (pinfunction "2_2") (pintype "passive"))
      (node (ref "C16") (pin "2") (pinfunction "2_2") (pintype "passive"))
      (node (ref "C19") (pin "2") (pinfunction "2_2") (pintype "passive"))
      (node (ref "C20") (pin "+") (pinfunction "+_+") (pintype "passive"))
      (node (ref "C3") (pin "2") (pinfunction "2_2") (pintype "passive"))
      (node (ref "C4") (pin "2") (pinfunction "2_2") (pintype "passive"))
      (node (ref "C5") (pin "1") (pinfunction "1_1") (pintype "passive"))
      (node (ref "C6") (pin "1") (pinfunction "1_1") (pintype "passive"))
      (node (ref "C7") (pin "1") (pinfunction "1_1") (pintype "passive"))
      (node (ref "C8") (pin "1") (pinfunction "1_1") (pintype "passive"))
      (node (ref "C9") (pin "1") (pinfunction "1_1") (pintype "passive"))
      (node (ref "IC1") (pin "100") (pinfunction "VDD_100") (pintype "power_in"))
      (node (ref "IC1") (pin "11") (pinfunction "VDD_11") (pintype "power_in"))
      (node (ref "IC1") (pin "21") (pinfunction "VDDA_21") (pintype "power_in"))
      (node (ref "IC1") (pin "27") (pinfunction "VDD_27") (pintype "power_in"))
      (node (ref "IC1") (pin "50") (pinfunction "VDD_50") (pintype "power_in"))
      (node (ref "IC1") (pin "6") (pinfunction "VBAT_6") (pintype "passive"))
      (node (ref "IC1") (pin "75") (pinfunction "VDD_75") (pintype "power_in"))
      (node (ref "IC2") (pin "8") (pinfunction "VCC_8") (pintype "power_in"))
      (node (ref "IC3") (pin "2") (pinfunction "VOUT_2") (pintype "output"))
      (node (ref "ICSP") (pin "2") (pinfunction "2_2") (pintype "passive"))
      (node (ref "JP3") (pin "VCC") (pinfunction "VCC_VCC") (pintype "bidirectional"))
      (node (ref "POWER") (pin "2") (pinfunction "2_2") (pintype "passive"))
      (node (ref "R1") (pin "2") (pinfunction "2_2") (pintype "passive"))
      (node (ref "R13") (pin "2") (pinfunction "2_2") (pintype "passive"))
      (node (ref "R17") (pin "2") (pinfunction "2_2") (pintype "passive"))
      (node (ref "R18") (pin "2") (pinfunction "2_2") (pintype "passive"))
      (node (ref "R19") (pin "2") (pinfunction "2_2") (pintype "passive"))
      (node (ref "R20") (pin "2") (pinfunction "2_2") (pintype "passive"))
      (node (ref "R21") (pin "2") (pinfunction "2_2") (pintype "passive"))
      (node (ref "R22") (pin "2") (pinfunction "2_2") (pintype "passive"))
      (node (ref "R23") (pin "2") (pinfunction "2_2") (pintype "passive"))
      (node (ref "R24") (pin "2") (pinfunction "2_2") (pintype "passive"))
      (node (ref "R26") (pin "2") (pinfunction "2_2") (pintype "passive"))
      (node (ref "R28") (pin "1") (pinfunction "1_1") (pintype "passive"))
      (node (ref "R29") (pin "1") (pinfunction "1_1") (pintype "passive"))
      (node (ref "R30") (pin "1") (pinfunction "1_1") (pintype "passive"))
      (node (ref "R31") (pin "1") (pinfunction "1_1") (pintype "passive"))
      (node (ref "R32") (pin "2") (pinfunction "2_2") (pintype "passive"))
      (node (ref "R35") (pin "1") (pinfunction "1_1") (pintype "passive"))
      (node (ref "SH5") (pin "2") (pinfunction "P$2_2") (pintype "bidirectional"))
      (node (ref "U1") (pin "8") (pinfunction "VCC_8") (pintype "power_in"))
    )
    (net (code "93") (name "VIN") (class "Default")
      (node (ref "POWER") (pin "6") (pinfunction "6_6") (pintype "passive"))
    )
    (net (code "94") (name "VINP") (class "Default")
      (node (ref "C22") (pin "1") (pinfunction "1_1") (pintype "passive"))
      (node (ref "IC3") (pin "3") (pinfunction "VIN_3") (pintype "input"))
      (node (ref "JP11") (pin "2") (pinfunction "2_2") (pintype "passive"))
    )
    (net (code "95") (name "VREF+") (class "Default")
      (node (ref "IC1") (pin "20") (pinfunction "VREFPLUS_20") (pintype "passive"))
      (node (ref "R25") (pin "2") (pinfunction "2_2") (pintype "passive"))
    )
    (net (code "96") (name "VREF_ARDUINO") (class "Default")
      (node (ref "IOH") (pin "8") (pinfunction "8_8") (pintype "passive"))
      (node (ref "R25") (pin "1") (pinfunction "1_1") (pintype "passive"))
      (node (ref "R26") (pin "1") (pinfunction "1_1") (pintype "passive"))
    )
    (net (code "97") (name "unconnected-(IC1-JTDI-Pad77)") (class "Default")
      (node (ref "IC1") (pin "77") (pinfunction "JTDI_77") (pintype "input"))
    )
    (net (code "98") (name "unconnected-(IC1-JTDO-Pad89)") (class "Default")
      (node (ref "IC1") (pin "89") (pinfunction "JTDO_89") (pintype "output"))
    )
    (net (code "99") (name "unconnected-(IC1-PC0-Pad15)") (class "Default")
      (node (ref "IC1") (pin "15") (pinfunction "PC0_15") (pintype "bidirectional"))
    )
    (net (code "100") (name "unconnected-(IC1-PC3_C-Pad18)") (class "Default")
      (node (ref "IC1") (pin "18") (pinfunction "PC3_C_18") (pintype "passive"))
    )
    (net (code "101") (name "unconnected-(IC1-PC8-Pad65)") (class "Default")
      (node (ref "IC1") (pin "65") (pinfunction "PC8_65") (pintype "bidirectional"))
    )
    (net (code "102") (name "unconnected-(IC1-PC13-Pad7)") (class "Default")
      (node (ref "IC1") (pin "7") (pinfunction "PC13_7") (pintype "bidirectional"))
    )
    (net (code "103") (name "unconnected-(IC1-PC14-Pad8)") (class "Default")
      (node (ref "IC1") (pin "8") (pinfunction "PC14_8") (pintype "bidirectional"))
    )
    (net (code "104") (name "unconnected-(IC1-PC15-Pad9)") (class "Default")
      (node (ref "IC1") (pin "9") (pinfunction "PC15_9") (pintype "bidirectional"))
    )
    (net (code "105") (name "unconnected-(IC1-PD3-Pad84)") (class "Default")
      (node (ref "IC1") (pin "84") (pinfunction "PD3_84") (pintype "bidirectional"))
    )
    (net (code "106") (name "unconnected-(IC1-PD6-Pad87)") (class "Default")
      (node (ref "IC1") (pin "87") (pinfunction "PD6_87") (pintype "bidirectional"))
    )
    (net (code "107") (name "unconnected-(IC1-PD13-Pad60)") (class "Default")
      (node (ref "IC1") (pin "60") (pinfunction "PD13_60") (pintype "bidirectional"))
    )
    (net (code "108") (name "unconnected-(IC1-PE3-Pad2)") (class "Default")
      (node (ref "IC1") (pin "2") (pinfunction "PE3_2") (pintype "bidirectional"))
    )
    (net (code "109") (name "unconnected-(IC1-PE4-Pad3)") (class "Default")
      (node (ref "IC1") (pin "3") (pinfunction "PE4_3") (pintype "bidirectional"))
    )
    (net (code "110") (name "unconnected-(IC1-PE5-Pad4)") (class "Default")
      (node (ref "IC1") (pin "4") (pinfunction "PE5_4") (pintype "bidirectional"))
    )
    (net (code "111") (name "unconnected-(IC1-PE6-Pad5)") (class "Default")
      (node (ref "IC1") (pin "5") (pinfunction "PE6_5") (pintype "bidirectional"))
    )
    (net (code "112") (name "unconnected-(IC1-PE11-Pad41)") (class "Default")
      (node (ref "IC1") (pin "41") (pinfunction "PE11_41") (pintype "bidirectional"))
    )
    (net (code "113") (name "unconnected-(IC1-PH0-Pad12)") (class "Default")
      (node (ref "IC1") (pin "12") (pinfunction "PH0_12") (pintype "bidirectional"))
    )
    (net (code "114") (name "unconnected-(IC1-PH1-Pad13)") (class "Default")
      (node (ref "IC1") (pin "13") (pinfunction "PH1_13") (pintype "bidirectional"))
    )
  )
)
